# Substractor.net
KiCad netlist of a schematic drawn in Altium Designer
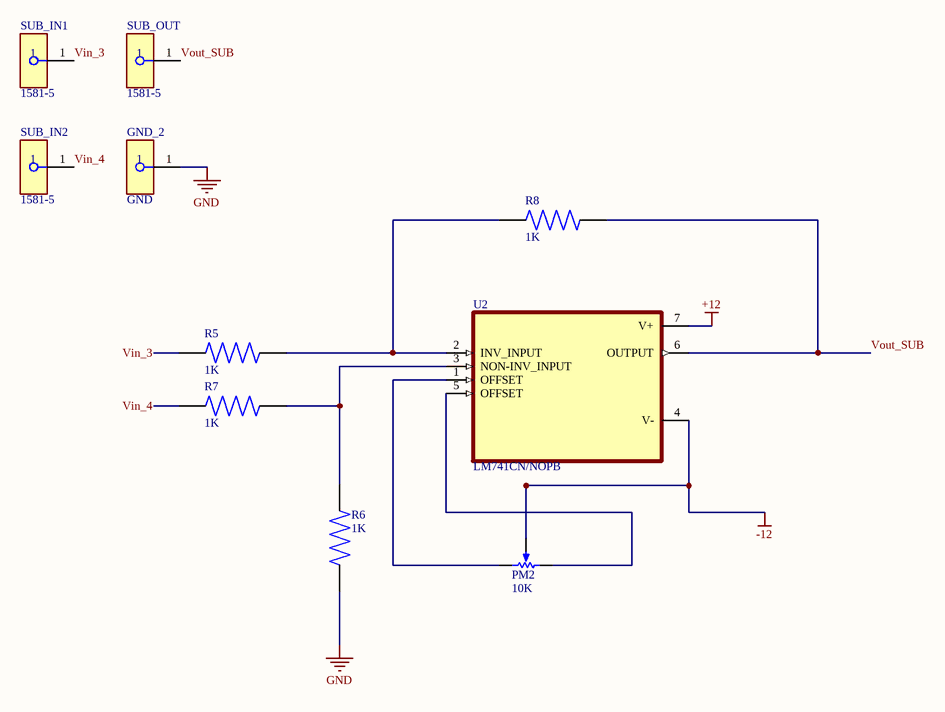
[diagram p0: Substractor.SchDoc]

(export (version "E")
  (design (tool "Eeschema 10.0.6"))
  (components
    (comp (ref "GND_2")
      (value "GND")
      (footprint "FP-1581-5-MFG")
      (description "CONN BANANA JACK TURRET GREEN")
      (libsource (lib "Altium Content Vault") (part "c5c826e0c4b67fe3b42ef77f2d4decc"))
    )
    (comp (ref "PM2")
      (value "10K")
      (footprint "PCBComponent_1")
      (libsource (lib "Integrated_Library1") (part "Component_1"))
    )
    (comp (ref "R5")
      (value "1K")
      (footprint "RESAD1100W55L680D260")
      (description "1.07 kOhms Â±1% 0.25W, 1/4W Through Hole Resistor Axial - Metal Film")
      (fields (field (name "MF") "Yageo") (field (name "MP") "MFR-25FBF52-1K"))
      (libsource (lib "MFR-25FBF52-1K") (part "MFR-25FBF52-1K"))
    )
    (comp (ref "R6")
      (value "1K")
      (footprint "RESAD1100W55L680D260")
      (description "1.07 kOhms Â±1% 0.25W, 1/4W Through Hole Resistor Axial - Metal Film")
      (fields (field (name "MF") "Yageo") (field (name "MP") "MFR-25FBF52-1K"))
      (libsource (lib "MFR-25FBF52-1K") (part "MFR-25FBF52-1K"))
    )
    (comp (ref "R7")
      (value "1K")
      (footprint "RESAD1100W55L680D260")
      (description "1.07 kOhms Â±1% 0.25W, 1/4W Through Hole Resistor Axial - Metal Film")
      (fields (field (name "MF") "Yageo") (field (name "MP") "MFR-25FBF52-1K"))
      (libsource (lib "MFR-25FBF52-1K") (part "MFR-25FBF52-1K"))
    )
    (comp (ref "R8")
      (value "1K")
      (footprint "RESAD1100W55L680D260")
      (description "1.07 kOhms Â±1% 0.25W, 1/4W Through Hole Resistor Axial - Metal Film")
      (fields (field (name "MF") "Yageo") (field (name "MP") "MFR-25FBF52-1K"))
      (libsource (lib "MFR-25FBF52-1K") (part "MFR-25FBF52-1K"))
    )
    (comp (ref "SUB_IN1")
      (value "1581-5")
      (footprint "FP-1581-5-MFG")
      (description "CONN BANANA JACK TURRET GREEN")
      (libsource (lib "Altium Content Vault") (part "c5c826e0c4b67fe3b42ef77f2d4decc"))
    )
    (comp (ref "SUB_IN2")
      (value "1581-5")
      (footprint "FP-1581-5-MFG")
      (description "CONN BANANA JACK TURRET GREEN")
      (libsource (lib "Altium Content Vault") (part "c5c826e0c4b67fe3b42ef77f2d4decc"))
    )
    (comp (ref "SUB_OUT")
      (value "1581-5")
      (footprint "FP-1581-5-MFG")
      (description "CONN BANANA JACK TURRET GREEN")
      (libsource (lib "Altium Content Vault") (part "c5c826e0c4b67fe3b42ef77f2d4decc"))
    )
    (comp (ref "U2")
      (value "LM741CN/NOPB")
      (footprint "DIP794W45P254L959H508Q8")
      (description "Single, 44-V, 1-MHz operational amplifier")
      (fields (field (name "MF") "Texas Instruments"))
      (libsource (lib "LM741CN_NOPB (1)") (part "LM741CN/NOPB"))
    )
  )
  (nets
    (net (code "1") (name "+12") (class "Default")
      (node (ref "U2") (pin "7") (pinfunction "V+_7") (pintype "power_in"))
    )
    (net (code "2") (name "-12") (class "Default")
      (node (ref "PM2") (pin "2") (pinfunction "S_2") (pintype "passive"))
      (node (ref "U2") (pin "4") (pinfunction "V-_4") (pintype "power_in"))
    )
    (net (code "3") (name "/Vin_3") (class "Default")
      (node (ref "R5") (pin "1") (pinfunction "1_1") (pintype "passive"))
      (node (ref "SUB_IN1") (pin "1") (pinfunction "1_1") (pintype "passive"))
    )
    (net (code "4") (name "/Vin_4") (class "Default")
      (node (ref "R7") (pin "1") (pinfunction "1_1") (pintype "passive"))
      (node (ref "SUB_IN2") (pin "1") (pinfunction "1_1") (pintype "passive"))
    )
    (net (code "5") (name "/Vout_SUB") (class "Default")
      (node (ref "R8") (pin "2") (pinfunction "2_2") (pintype "passive"))
      (node (ref "SUB_OUT") (pin "1") (pinfunction "1_1") (pintype "passive"))
      (node (ref "U2") (pin "6") (pinfunction "OUTPUT_6") (pintype "output"))
    )
    (net (code "6") (name "GND") (class "Default")
      (node (ref "GND_2") (pin "1") (pinfunction "1_1") (pintype "passive"))
      (node (ref "R6") (pin "1") (pinfunction "1_1") (pintype "passive"))
    )
    (net (code "7") (name "Net-(PM2-CCW)") (class "Default")
      (node (ref "PM2") (pin "1") (pinfunction "CCW_1") (pintype "passive"))
      (node (ref "U2") (pin "5") (pinfunction "OFFSET_5") (pintype "input"))
    )
    (net (code "8") (name "Net-(PM2-CW)") (class "Default")
      (node (ref "PM2") (pin "3") (pinfunction "CW_3") (pintype "passive"))
      (node (ref "U2") (pin "1") (pinfunction "OFFSET_1") (pintype "input"))
    )
    (net (code "9") (name "Net-(U2-INV_INPUT)") (class "Default")
      (node (ref "R5") (pin "2") (pinfunction "2_2") (pintype "passive"))
      (node (ref "R8") (pin "1") (pinfunction "1_1") (pintype "passive"))
      (node (ref "U2") (pin "2") (pinfunction "INV_INPUT_2") (pintype "input"))
    )
    (net (code "10") (name "Net-(U2-NON-INV_INPUT)") (class "Default")
      (node (ref "R6") (pin "2") (pinfunction "2_2") (pintype "passive"))
      (node (ref "R7") (pin "2") (pinfunction "2_2") (pintype "passive"))
      (node (ref "U2") (pin "3") (pinfunction "NON-INV_INPUT_3") (pintype "input"))
    )
  )
)
